# SCH_GPS_Tracker_TTGO_2024-01-23.net
KiCad netlist of a schematic drawn in EasyEDA
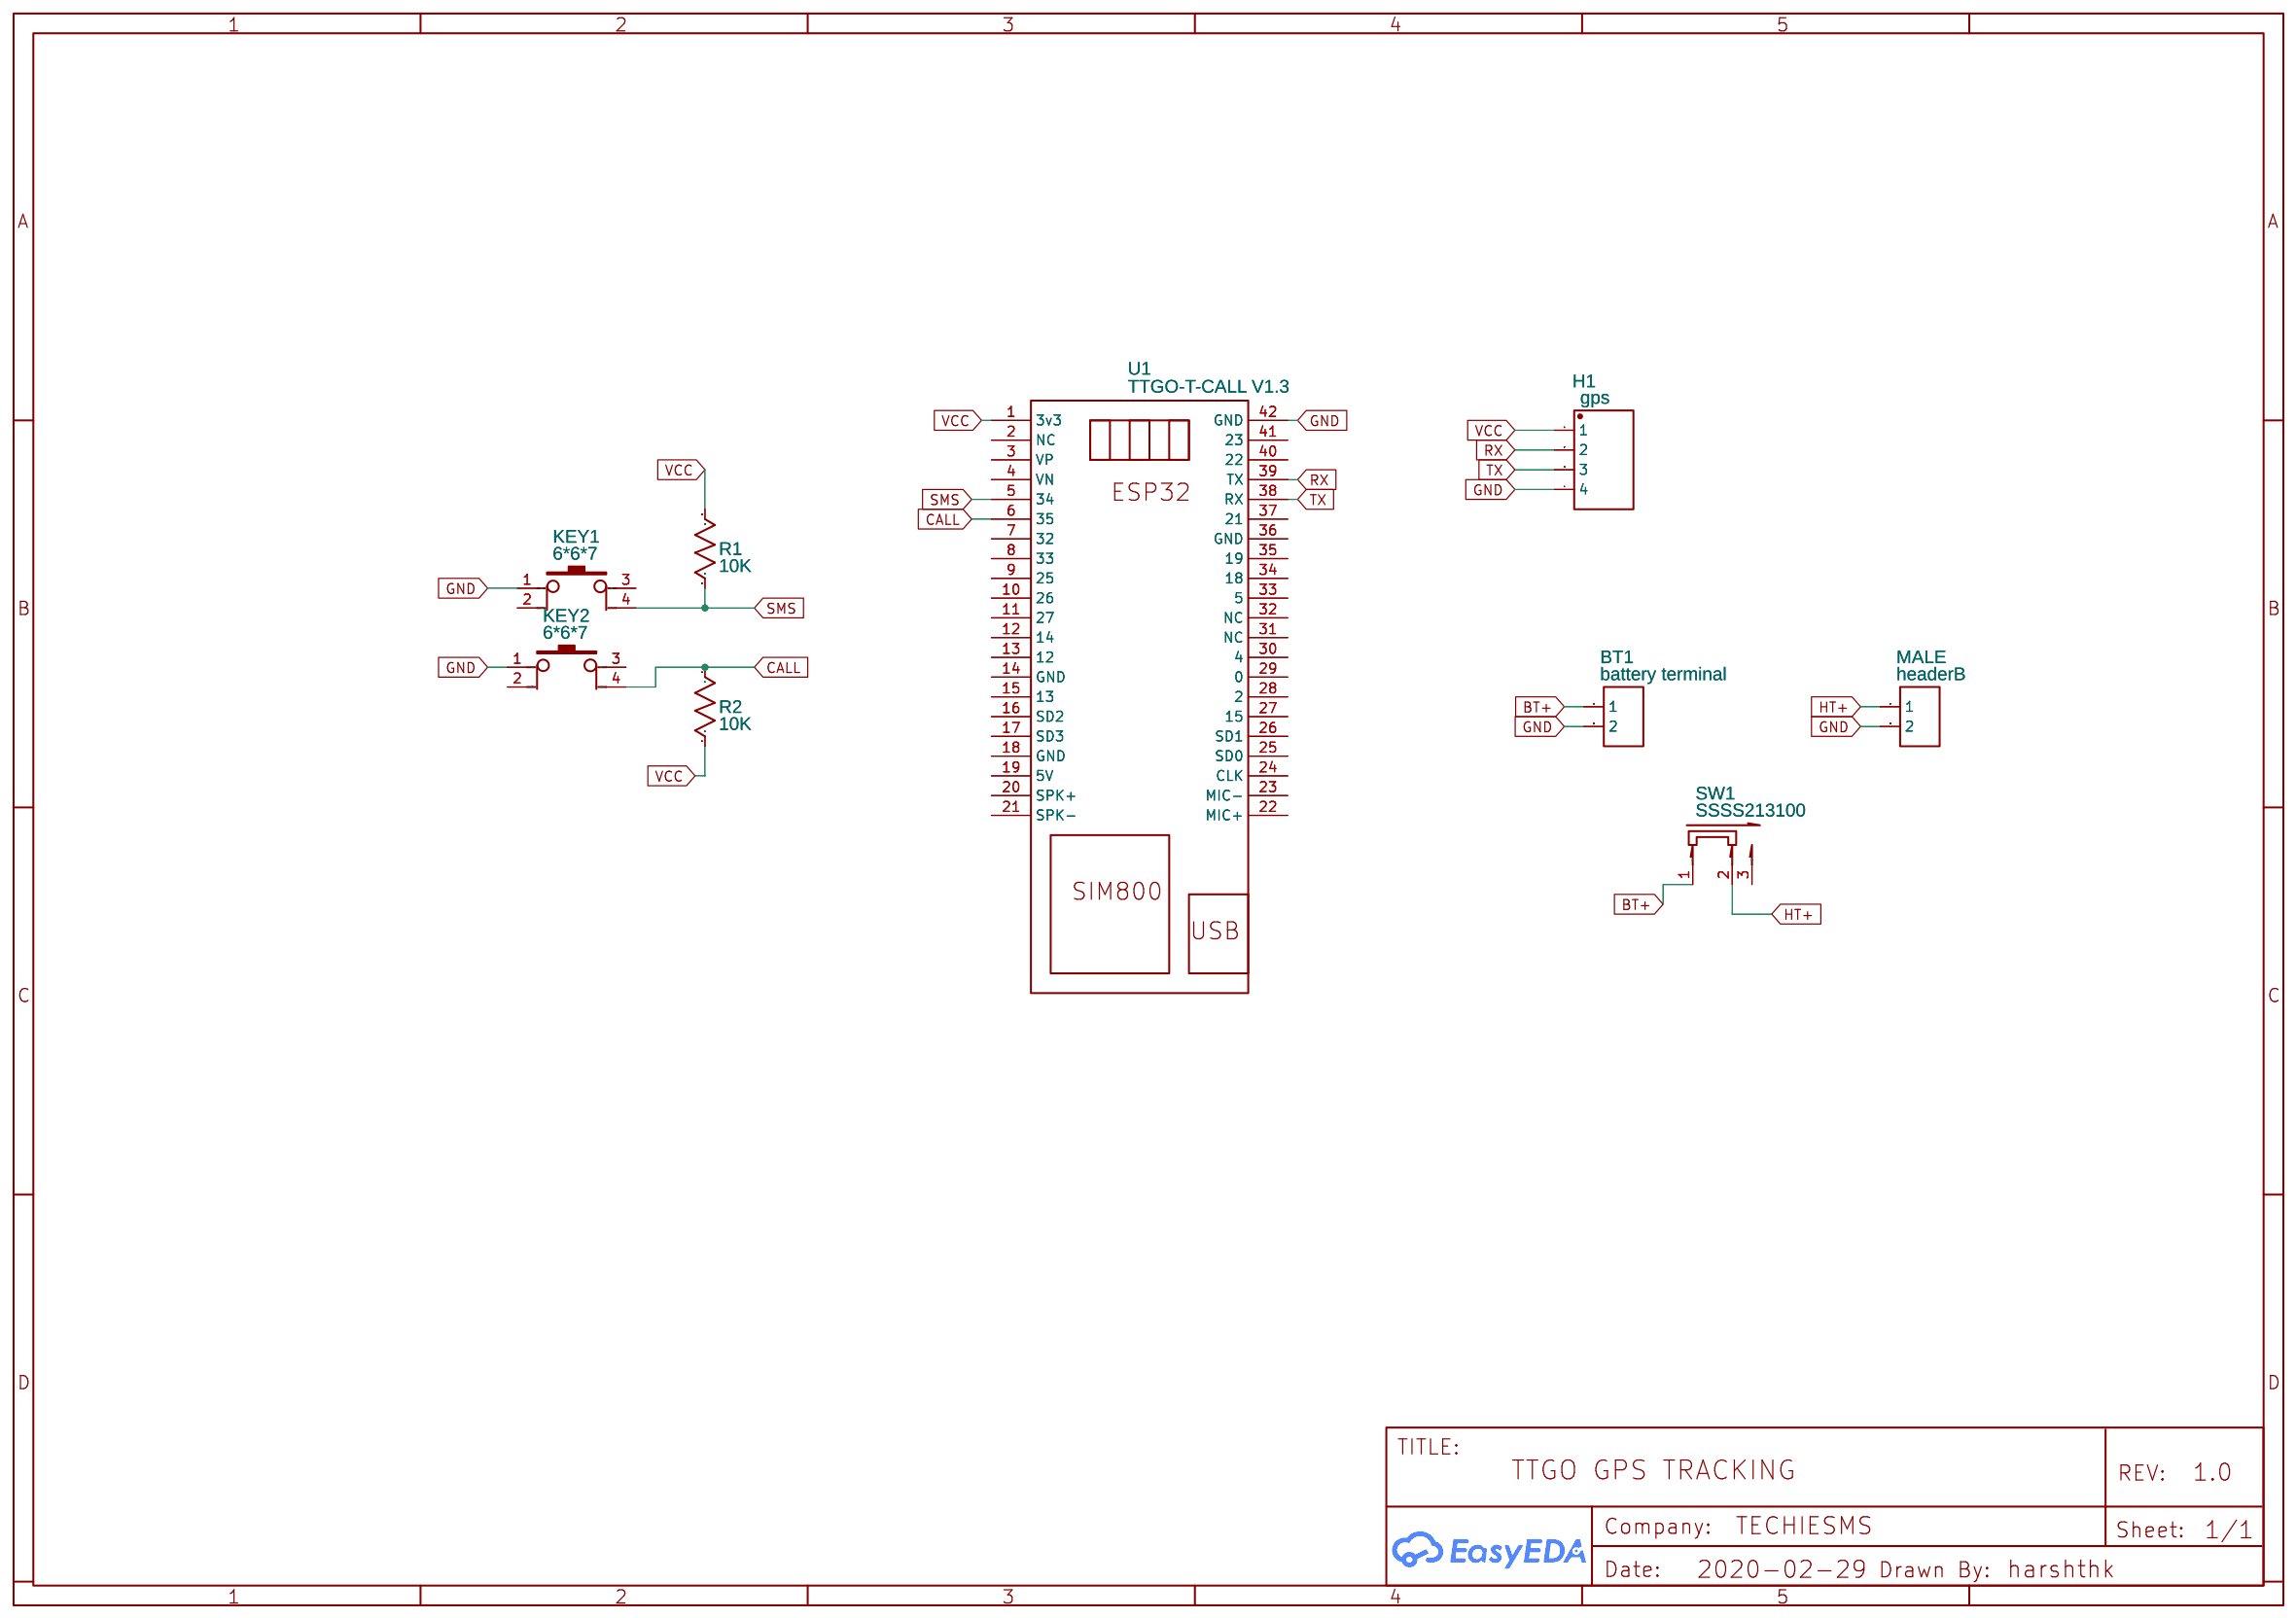
[diagram p0: schematic sheet]

(export (version "E")
  (design (tool "Eeschema 10.0.6"))
  (components
    (comp (ref "BT1")
      (value "battery terminal")
      (fields (field (name "Manufacturer Part") "2.54-1*2PFemale") (field (name "Manufacturer") "BOOMELE"))
      (libsource (lib "") (part "Header-Female-2.54_1x2_1"))
    )
    (comp (ref "H1")
      (value "gps")
      (fields
        (field (name "Manufacturer Part") "210S-1*4P L=11.6MMGold-plated black")
        (field (name "Manufacturer") "Ckmtw")
      )
      (libsource (lib "") (part "Header-Male-2.54_1x4"))
    )
    (comp (ref "KEY1")
      (value "6*6*7")
      (fields (field (name "Manufacturer") "ReliaPro"))
      (libsource (lib "") (part "6*6*7"))
    )
    (comp (ref "KEY2")
      (value "6*6*7")
      (fields (field (name "Manufacturer") "ReliaPro"))
      (libsource (lib "") (part "6*6*7"))
    )
    (comp (ref "MALE")
      (value "headerB")
      (fields (field (name "Manufacturer Part") "2.54-1*2PFemale") (field (name "Manufacturer") "BOOMELE"))
      (libsource (lib "") (part "Header-Female-2.54_1x2"))
    )
    (comp (ref "R1") (value "10K") (libsource (lib "") (part "Res_AXIAL-0.3(1/8W)_US")))
    (comp (ref "R2") (value "10K") (libsource (lib "") (part "Res_AXIAL-0.3(1/8W)_US_1")))
    (comp (ref "SW1")
      (value "SSSS213100")
      (fields (field (name "Manufacturer") "ALPS"))
      (libsource (lib "") (part "SSSS213100"))
    )
    (comp (ref "U1") (value "TTGO-T-CALL V1.3") (libsource (lib "") (part "TTGO-T-CALL V1.3")))
  )
  (nets
    (net (code "1") (name "BT+") (class "Default")
      (node (ref "BT1") (pin "1") (pinfunction "1_1") (pintype "input"))
      (node (ref "SW1") (pin "1") (pinfunction "1_1") (pintype "unspecified"))
    )
    (net (code "2") (name "CALL") (class "Default")
      (node (ref "KEY2") (pin "4") (pinfunction "4_4") (pintype "input"))
      (node (ref "R2") (pin "1") (pinfunction "1_1") (pintype "unspecified"))
      (node (ref "U1") (pin "6") (pinfunction "35_6") (pintype "unspecified"))
    )
    (net (code "3") (name "GND") (class "Default")
      (node (ref "BT1") (pin "2") (pinfunction "2_2") (pintype "input"))
      (node (ref "H1") (pin "4") (pinfunction "4_4") (pintype "unspecified"))
      (node (ref "KEY1") (pin "1") (pinfunction "1_1") (pintype "input"))
      (node (ref "KEY2") (pin "1") (pinfunction "1_1") (pintype "input"))
      (node (ref "MALE") (pin "2") (pinfunction "2_2") (pintype "input"))
      (node (ref "U1") (pin "42") (pinfunction "GND_42") (pintype "unspecified"))
    )
    (net (code "4") (name "HT+") (class "Default")
      (node (ref "MALE") (pin "1") (pinfunction "1_1") (pintype "input"))
      (node (ref "SW1") (pin "2") (pinfunction "2_2") (pintype "unspecified"))
    )
    (net (code "5") (name "RX") (class "Default")
      (node (ref "H1") (pin "2") (pinfunction "2_2") (pintype "unspecified"))
      (node (ref "U1") (pin "39") (pinfunction "TX_39") (pintype "unspecified"))
    )
    (net (code "6") (name "SMS") (class "Default")
      (node (ref "KEY1") (pin "4") (pinfunction "4_4") (pintype "input"))
      (node (ref "R1") (pin "1") (pinfunction "1_1") (pintype "unspecified"))
      (node (ref "U1") (pin "5") (pinfunction "34_5") (pintype "unspecified"))
    )
    (net (code "7") (name "TX") (class "Default")
      (node (ref "H1") (pin "3") (pinfunction "3_3") (pintype "unspecified"))
      (node (ref "U1") (pin "38") (pinfunction "RX_38") (pintype "unspecified"))
    )
    (net (code "8") (name "VCC") (class "Default")
      (node (ref "H1") (pin "1") (pinfunction "1_1") (pintype "unspecified"))
      (node (ref "R1") (pin "2") (pinfunction "2_2") (pintype "unspecified"))
      (node (ref "R2") (pin "2") (pinfunction "2_2") (pintype "unspecified"))
      (node (ref "U1") (pin "1") (pinfunction "3v3_1") (pintype "unspecified"))
    )
    (net (code "9") (name "unconnected-(KEY1-Pad2)") (class "Default")
      (node (ref "KEY1") (pin "2") (pinfunction "2_2") (pintype "input"))
    )
    (net (code "10") (name "unconnected-(KEY1-Pad3)") (class "Default")
      (node (ref "KEY1") (pin "3") (pinfunction "3_3") (pintype "input"))
    )
    (net (code "11") (name "unconnected-(KEY2-Pad2)") (class "Default")
      (node (ref "KEY2") (pin "2") (pinfunction "2_2") (pintype "input"))
    )
    (net (code "12") (name "unconnected-(KEY2-Pad3)") (class "Default")
      (node (ref "KEY2") (pin "3") (pinfunction "3_3") (pintype "input"))
    )
    (net (code "13") (name "unconnected-(SW1-Pad3)") (class "Default")
      (node (ref "SW1") (pin "3") (pinfunction "3_3") (pintype "unspecified"))
    )
    (net (code "14") (name "unconnected-(U1-0-Pad29)") (class "Default")
      (node (ref "U1") (pin "29") (pinfunction "0_29") (pintype "unspecified"))
    )
    (net (code "15") (name "unconnected-(U1-2-Pad28)") (class "Default")
      (node (ref "U1") (pin "28") (pinfunction "2_28") (pintype "unspecified"))
    )
    (net (code "16") (name "unconnected-(U1-4-Pad30)") (class "Default")
      (node (ref "U1") (pin "30") (pinfunction "4_30") (pintype "unspecified"))
    )
    (net (code "17") (name "unconnected-(U1-5-Pad33)") (class "Default")
      (node (ref "U1") (pin "33") (pinfunction "5_33") (pintype "unspecified"))
    )
    (net (code "18") (name "unconnected-(U1-5V-Pad19)") (class "Default")
      (node (ref "U1") (pin "19") (pinfunction "5V_19") (pintype "unspecified"))
    )
    (net (code "19") (name "unconnected-(U1-12-Pad13)") (class "Default")
      (node (ref "U1") (pin "13") (pinfunction "12_13") (pintype "unspecified"))
    )
    (net (code "20") (name "unconnected-(U1-13-Pad15)") (class "Default")
      (node (ref "U1") (pin "15") (pinfunction "13_15") (pintype "unspecified"))
    )
    (net (code "21") (name "unconnected-(U1-14-Pad12)") (class "Default")
      (node (ref "U1") (pin "12") (pinfunction "14_12") (pintype "unspecified"))
    )
    (net (code "22") (name "unconnected-(U1-15-Pad27)") (class "Default")
      (node (ref "U1") (pin "27") (pinfunction "15_27") (pintype "unspecified"))
    )
    (net (code "23") (name "unconnected-(U1-18-Pad34)") (class "Default")
      (node (ref "U1") (pin "34") (pinfunction "18_34") (pintype "unspecified"))
    )
    (net (code "24") (name "unconnected-(U1-19-Pad35)") (class "Default")
      (node (ref "U1") (pin "35") (pinfunction "19_35") (pintype "unspecified"))
    )
    (net (code "25") (name "unconnected-(U1-21-Pad37)") (class "Default")
      (node (ref "U1") (pin "37") (pinfunction "21_37") (pintype "unspecified"))
    )
    (net (code "26") (name "unconnected-(U1-22-Pad40)") (class "Default")
      (node (ref "U1") (pin "40") (pinfunction "22_40") (pintype "unspecified"))
    )
    (net (code "27") (name "unconnected-(U1-23-Pad41)") (class "Default")
      (node (ref "U1") (pin "41") (pinfunction "23_41") (pintype "unspecified"))
    )
    (net (code "28") (name "unconnected-(U1-25-Pad9)") (class "Default")
      (node (ref "U1") (pin "9") (pinfunction "25_9") (pintype "unspecified"))
    )
    (net (code "29") (name "unconnected-(U1-26-Pad10)") (class "Default")
      (node (ref "U1") (pin "10") (pinfunction "26_10") (pintype "unspecified"))
    )
    (net (code "30") (name "unconnected-(U1-27-Pad11)") (class "Default")
      (node (ref "U1") (pin "11") (pinfunction "27_11") (pintype "unspecified"))
    )
    (net (code "31") (name "unconnected-(U1-32-Pad7)") (class "Default")
      (node (ref "U1") (pin "7") (pinfunction "32_7") (pintype "unspecified"))
    )
    (net (code "32") (name "unconnected-(U1-33-Pad8)") (class "Default")
      (node (ref "U1") (pin "8") (pinfunction "33_8") (pintype "unspecified"))
    )
    (net (code "33") (name "unconnected-(U1-CLK-Pad24)") (class "Default")
      (node (ref "U1") (pin "24") (pinfunction "CLK_24") (pintype "unspecified"))
    )
    (net (code "34") (name "unconnected-(U1-GND-Pad14)") (class "Default")
      (node (ref "U1") (pin "14") (pinfunction "GND_14") (pintype "unspecified"))
    )
    (net (code "35") (name "unconnected-(U1-GND-Pad18)") (class "Default")
      (node (ref "U1") (pin "18") (pinfunction "GND_18") (pintype "unspecified"))
    )
    (net (code "36") (name "unconnected-(U1-GND-Pad36)") (class "Default")
      (node (ref "U1") (pin "36") (pinfunction "GND_36") (pintype "unspecified"))
    )
    (net (code "37") (name "unconnected-(U1-MIC+-Pad22)") (class "Default")
      (node (ref "U1") (pin "22") (pinfunction "MIC+_22") (pintype "unspecified"))
    )
    (net (code "38") (name "unconnected-(U1-MIC--Pad23)") (class "Default")
      (node (ref "U1") (pin "23") (pinfunction "MIC-_23") (pintype "unspecified"))
    )
    (net (code "39") (name "unconnected-(U1-NC-Pad2)") (class "Default")
      (node (ref "U1") (pin "2") (pinfunction "NC_2") (pintype "unspecified"))
    )
    (net (code "40") (name "unconnected-(U1-NC-Pad31)") (class "Default")
      (node (ref "U1") (pin "31") (pinfunction "NC_31") (pintype "unspecified"))
    )
    (net (code "41") (name "unconnected-(U1-NC-Pad32)") (class "Default")
      (node (ref "U1") (pin "32") (pinfunction "NC_32") (pintype "unspecified"))
    )
    (net (code "42") (name "unconnected-(U1-SD0-Pad25)") (class "Default")
      (node (ref "U1") (pin "25") (pinfunction "SD0_25") (pintype "unspecified"))
    )
    (net (code "43") (name "unconnected-(U1-SD1-Pad26)") (class "Default")
      (node (ref "U1") (pin "26") (pinfunction "SD1_26") (pintype "unspecified"))
    )
    (net (code "44") (name "unconnected-(U1-SD2-Pad16)") (class "Default")
      (node (ref "U1") (pin "16") (pinfunction "SD2_16") (pintype "unspecified"))
    )
    (net (code "45") (name "unconnected-(U1-SD3-Pad17)") (class "Default")
      (node (ref "U1") (pin "17") (pinfunction "SD3_17") (pintype "unspecified"))
    )
    (net (code "46") (name "unconnected-(U1-SPK+-Pad20)") (class "Default")
      (node (ref "U1") (pin "20") (pinfunction "SPK+_20") (pintype "unspecified"))
    )
    (net (code "47") (name "unconnected-(U1-SPK--Pad21)") (class "Default")
      (node (ref "U1") (pin "21") (pinfunction "SPK-_21") (pintype "unspecified"))
    )
    (net (code "48") (name "unconnected-(U1-VN-Pad4)") (class "Default")
      (node (ref "U1") (pin "4") (pinfunction "VN_4") (pintype "unspecified"))
    )
    (net (code "49") (name "unconnected-(U1-VP-Pad3)") (class "Default")
      (node (ref "U1") (pin "3") (pinfunction "VP_3") (pintype "unspecified"))
    )
  )
)
